# atxmega.net
KiCad netlist of a schematic drawn in Altium Designer
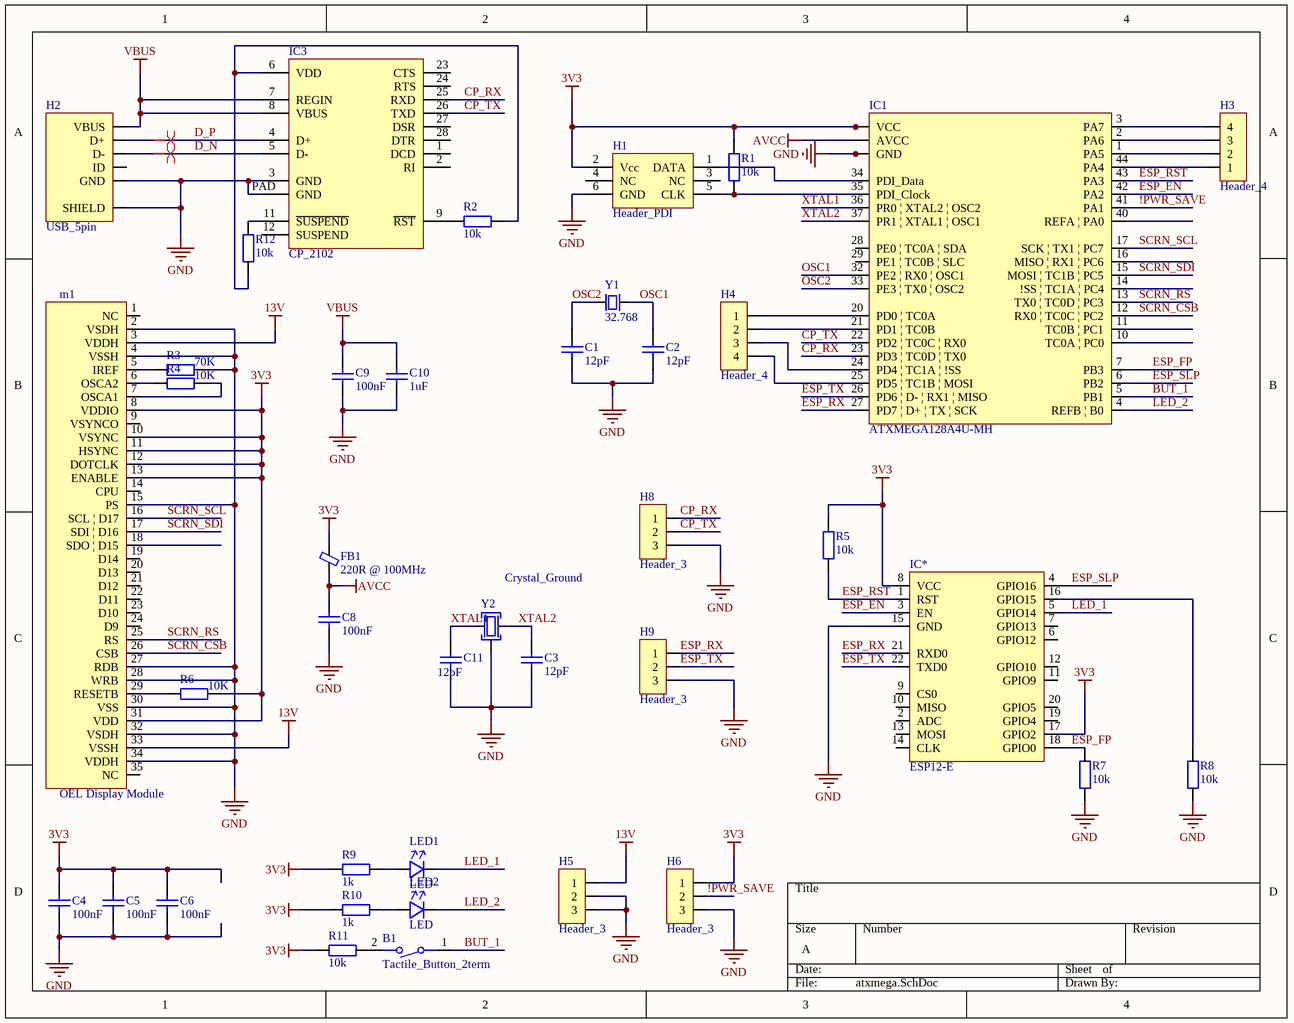
[diagram p0: atxmega.SchDoc]

(export (version "E")
  (design (tool "Eeschema 10.0.6"))
  (components
    (comp (ref "B1")
      (value "Tactile_Button_2term")
      (footprint "TACTILE_MINATUE_SMD_3.5x6mm")
      (libsource (lib "AranCustomFootprints") (part "Tactile_Button_2term"))
    )
    (comp (ref "C1")
      (value "12pF")
      (footprint "C0402")
      (description "Schematic symbol of a capacitor")
      (libsource (lib "AranCustomFootprints") (part "Capacitor"))
    )
    (comp (ref "C2")
      (value "12pF")
      (footprint "C0402")
      (description "Schematic symbol of a capacitor")
      (libsource (lib "AranCustomFootprints") (part "Capacitor"))
    )
    (comp (ref "C3")
      (value "12pF")
      (footprint "C0402")
      (description "Schematic symbol of a capacitor")
      (libsource (lib "AranCustomFootprints") (part "Capacitor"))
    )
    (comp (ref "C4")
      (value "100nF")
      (footprint "C0603")
      (description "Schematic symbol of a capacitor")
      (libsource (lib "AranCustomFootprints") (part "Capacitor"))
    )
    (comp (ref "C5")
      (value "100nF")
      (footprint "C0603")
      (description "Schematic symbol of a capacitor")
      (libsource (lib "AranCustomFootprints") (part "Capacitor"))
    )
    (comp (ref "C6")
      (value "100nF")
      (footprint "C0603")
      (description "Schematic symbol of a capacitor")
      (libsource (lib "AranCustomFootprints") (part "Capacitor"))
    )
    (comp (ref "C8")
      (value "100nF")
      (footprint "C0603")
      (description "Schematic symbol of a capacitor")
      (libsource (lib "AranCustomFootprints") (part "Capacitor"))
    )
    (comp (ref "C9")
      (value "100nF")
      (footprint "C0603")
      (description "Schematic symbol of a capacitor")
      (libsource (lib "AranCustomFootprints") (part "Capacitor"))
    )
    (comp (ref "C10")
      (value "1uF")
      (footprint "C0603")
      (description "Schematic symbol of a capacitor")
      (libsource (lib "AranCustomFootprints") (part "Capacitor"))
    )
    (comp (ref "C11")
      (value "12pF")
      (footprint "C0402")
      (description "Schematic symbol of a capacitor")
      (libsource (lib "AranCustomFootprints") (part "Capacitor"))
    )
    (comp (ref "FB1")
      (value "220R @ 100MHz")
      (footprint "L0805")
      (libsource (lib "AranCustomFootprints") (part "Ferrite"))
    )
    (comp (ref "H1")
      (value "Header_PDI")
      (footprint "6-HEADER_BOXED")
      (description "6-pin Boxed header with pinout used for PDI programming by Atmel programmers")
      (libsource (lib "AranCustomFootprints") (part "Header_PDI"))
    )
    (comp (ref "H2")
      (value "USB_5pin")
      (footprint "USB_Micro_B_RECEPTABLE_FCI")
      (description "5 Pins USB Connector")
      (libsource (lib "AranCustomFootprints") (part "USB_5pin"))
    )
    (comp (ref "H3")
      (value "Header_4")
      (footprint "Header_MALE_4")
      (description "Generic 4pin header symbol")
      (libsource (lib "AranCustomFootprints") (part "Header_4"))
    )
    (comp (ref "H4")
      (value "Header_4")
      (footprint "Header_MALE_4")
      (description "Generic 4pin header symbol")
      (libsource (lib "") (part "Header_4_1"))
    )
    (comp (ref "H5")
      (value "Header_3")
      (footprint "Header_MALE_3")
      (description "Generic 3pin header symbol")
      (libsource (lib "AranCustomFootprints") (part "Header_3"))
    )
    (comp (ref "H6")
      (value "Header_3")
      (footprint "Header_MALE_3")
      (description "Generic 3pin header symbol")
      (libsource (lib "AranCustomFootprints") (part "Header_3"))
    )
    (comp (ref "H8")
      (value "Header_3")
      (footprint "Header_MALE_3")
      (description "Generic 3pin header symbol")
      (libsource (lib "AranCustomFootprints") (part "Header_3"))
    )
    (comp (ref "H9")
      (value "Header_3")
      (footprint "Header_MALE_3")
      (description "Generic 3pin header symbol")
      (libsource (lib "AranCustomFootprints") (part "Header_3"))
    )
    (comp (ref "IC*") (value "ESP12-E") (footprint "ESP12-E") (libsource (lib "elmarlib") (part "ESP12-E")))
    (comp (ref "IC1")
      (value "ATXMEGA128A4U-MH")
      (footprint "44-VFQFN-E")
      (description "AVR AVR® XMEGA® A4U Microcontroller IC 8/16-Bit 32MHz 128KB (64K x 16) FLASH 44-VQFN (7x7)")
      (libsource (lib "elmarlib") (part "ATXMEGA128A4U-MH"))
    )
    (comp (ref "IC3")
      (value "CP_2102")
      (footprint "28-QFN_Exposed_pad")
      (description "Single chip USB to UART Bridge")
      (libsource (lib "AranCustomFootprints") (part "CP_2102"))
    )
    (comp (ref "LED1")
      (value "LED")
      (footprint "0603_LED")
      (description "Schematic symbol of a LED")
      (libsource (lib "AranCustomFootprints") (part "LED"))
    )
    (comp (ref "LED2")
      (value "LED")
      (footprint "0603_LED")
      (description "Schematic symbol of a LED")
      (libsource (lib "AranCustomFootprints") (part "LED"))
    )
    (comp (ref "m1")
      (value "OEL Display Module")
      (footprint "FFC-35-pin-0.5")
      (description "Part ID: UG-6028GDEAF01")
      (libsource (lib "elmarlib") (part "OEL Display Module"))
    )
    (comp (ref "R1")
      (value "10k")
      (footprint "R0603")
      (description "Schematic symbol of a resistor")
      (libsource (lib "AranCustomFootprints") (part "Resistor"))
    )
    (comp (ref "R2")
      (value "10k")
      (footprint "R0603")
      (description "Schematic symbol of a resistor")
      (libsource (lib "AranCustomFootprints") (part "Resistor"))
    )
    (comp (ref "R3")
      (value "70K")
      (footprint "R0603")
      (description "Schematic symbol of a resistor")
      (libsource (lib "AranCustomFootprints") (part "Resistor"))
    )
    (comp (ref "R4")
      (value "10K")
      (footprint "R0603")
      (description "Schematic symbol of a resistor")
      (libsource (lib "AranCustomFootprints") (part "Resistor"))
    )
    (comp (ref "R5")
      (value "10k")
      (footprint "R0603")
      (description "Schematic symbol of a resistor")
      (libsource (lib "AranCustomFootprints") (part "Resistor"))
    )
    (comp (ref "R6")
      (value "10K")
      (footprint "R0603")
      (description "Schematic symbol of a resistor")
      (libsource (lib "AranCustomFootprints") (part "Resistor"))
    )
    (comp (ref "R7")
      (value "10k")
      (footprint "R0603")
      (description "Schematic symbol of a resistor")
      (libsource (lib "AranCustomFootprints") (part "Resistor"))
    )
    (comp (ref "R8")
      (value "10k")
      (footprint "R0603")
      (description "Schematic symbol of a resistor")
      (libsource (lib "AranCustomFootprints") (part "Resistor"))
    )
    (comp (ref "R9")
      (value "1k")
      (footprint "R0603")
      (description "Schematic symbol of a resistor")
      (libsource (lib "AranCustomFootprints") (part "Resistor"))
    )
    (comp (ref "R10")
      (value "1k")
      (footprint "R0603")
      (description "Schematic symbol of a resistor")
      (libsource (lib "AranCustomFootprints") (part "Resistor"))
    )
    (comp (ref "R11")
      (value "10k")
      (footprint "R0603")
      (description "Schematic symbol of a resistor")
      (libsource (lib "AranCustomFootprints") (part "Resistor"))
    )
    (comp (ref "R12")
      (value "10k")
      (footprint "R0603")
      (description "Schematic symbol of a resistor")
      (libsource (lib "AranCustomFootprints") (part "Resistor"))
    )
    (comp (ref "Y1")
      (value "32.768")
      (footprint "crystal_6.2x2.1x2.1")
      (description "32.768kHz ±20ppm Crystal 12.5pF 35 kOhm -10°C ~ 60°C Through Hole Cylindrical Can, Radial")
      (libsource (lib "elmarlib") (part "Abracon LLC AB26T-32.768KHZ"))
    )
    (comp (ref "Y2")
      (value "Crystal_Ground")
      (footprint "Crystal_3.2x2.5")
      (description "Schematic symbol of a 2pin crystal with case connection")
      (libsource (lib "AranCustomFootprints") (part "Crystal_Ground"))
    )
  )
  (nets
    (net (code "1") (name "/!PWR_SAVE") (class "Default")
      (node (ref "H6") (pin "2") (pinfunction "2_2") (pintype "passive"))
      (node (ref "IC1") (pin "41") (pinfunction "PA1_41") (pintype "passive"))
    )
    (net (code "2") (name "/BUT_1") (class "Default")
      (node (ref "B1") (pin "1") (pintype "passive"))
      (node (ref "IC1") (pin "5") (pinfunction "PB1_5") (pintype "passive"))
    )
    (net (code "3") (name "/CP_RX") (class "Default")
      (node (ref "H8") (pin "1") (pinfunction "1_1") (pintype "passive"))
      (node (ref "IC1") (pin "23") (pinfunction "PD3_¦_TC0D_¦_TX0_23") (pintype "passive"))
      (node (ref "IC3") (pin "25") (pinfunction "RXD_25") (pintype "passive"))
    )
    (net (code "4") (name "/CP_TX") (class "Default")
      (node (ref "H8") (pin "2") (pinfunction "2_2") (pintype "passive"))
      (node (ref "IC1") (pin "22") (pinfunction "PD2_¦_TC0C_¦_RX0_22") (pintype "passive"))
      (node (ref "IC3") (pin "26") (pinfunction "TXD_26") (pintype "passive"))
    )
    (net (code "5") (name "/D_N") (class "Default")
      (node (ref "H2") (pin "2") (pinfunction "D-_2") (pintype "passive"))
      (node (ref "IC3") (pin "5") (pinfunction "D-_5") (pintype "passive"))
    )
    (net (code "6") (name "/D_P") (class "Default")
      (node (ref "H2") (pin "3") (pinfunction "D+_3") (pintype "passive"))
      (node (ref "IC3") (pin "4") (pinfunction "D+_4") (pintype "passive"))
    )
    (net (code "7") (name "/ESP_EN") (class "Default")
      (node (ref "IC*") (pin "3") (pinfunction "EN_3") (pintype "passive"))
      (node (ref "IC1") (pin "42") (pinfunction "PA2_42") (pintype "passive"))
    )
    (net (code "8") (name "/ESP_FP") (class "Default")
      (node (ref "IC*") (pin "18") (pinfunction "GPIO0_18") (pintype "passive"))
      (node (ref "IC1") (pin "7") (pinfunction "PB3_7") (pintype "passive"))
      (node (ref "R7") (pin "1") (pinfunction "1_1") (pintype "passive"))
    )
    (net (code "9") (name "/ESP_RST") (class "Default")
      (node (ref "IC*") (pin "1") (pinfunction "RST_1") (pintype "passive"))
      (node (ref "IC1") (pin "43") (pinfunction "PA3_43") (pintype "passive"))
      (node (ref "R5") (pin "2") (pinfunction "2_2") (pintype "passive"))
    )
    (net (code "10") (name "/ESP_RX") (class "Default")
      (node (ref "H9") (pin "1") (pinfunction "1_1") (pintype "passive"))
      (node (ref "IC*") (pin "21") (pinfunction "RXD0_21") (pintype "passive"))
      (node (ref "IC1") (pin "27") (pinfunction "PD7_¦_D+_¦_TX_¦_SCK_27") (pintype "passive"))
    )
    (net (code "11") (name "/ESP_SLP") (class "Default")
      (node (ref "IC*") (pin "4") (pinfunction "GPIO16_4") (pintype "passive"))
      (node (ref "IC1") (pin "6") (pinfunction "PB2_6") (pintype "passive"))
    )
    (net (code "12") (name "/ESP_TX") (class "Default")
      (node (ref "H9") (pin "2") (pinfunction "2_2") (pintype "passive"))
      (node (ref "IC*") (pin "22") (pinfunction "TXD0_22") (pintype "passive"))
      (node (ref "IC1") (pin "26") (pinfunction "PD6_¦_D-_¦_RX1_¦_MISO_26") (pintype "passive"))
    )
    (net (code "13") (name "/LED_1") (class "Default")
      (node (ref "IC*") (pin "5") (pinfunction "GPIO14_5") (pintype "passive"))
      (node (ref "LED1") (pin "C") (pinfunction "Cathode_C") (pintype "passive"))
    )
    (net (code "14") (name "/LED_2") (class "Default")
      (node (ref "IC1") (pin "4") (pinfunction "REFB_¦_B0_4") (pintype "passive"))
      (node (ref "LED2") (pin "C") (pinfunction "Cathode_C") (pintype "passive"))
    )
    (net (code "15") (name "/OSC1") (class "Default")
      (node (ref "C2") (pin "1") (pinfunction "1_1") (pintype "passive"))
      (node (ref "IC1") (pin "32") (pinfunction "PE2_¦_RX0_¦_OSC1_32") (pintype "passive"))
      (node (ref "Y1") (pin "0") (pinfunction "XTAL2_0") (pintype "passive"))
    )
    (net (code "16") (name "/OSC2") (class "Default")
      (node (ref "C1") (pin "1") (pinfunction "1_1") (pintype "passive"))
      (node (ref "IC1") (pin "33") (pinfunction "PE3_¦_TX0_¦_OSC2_33") (pintype "passive"))
      (node (ref "Y1") (pin "1") (pinfunction "XTAL1_1") (pintype "passive"))
    )
    (net (code "17") (name "/SCRN_CSB") (class "Default")
      (node (ref "IC1") (pin "12") (pinfunction "RX0_¦_TC0C_¦_PC2_12") (pintype "passive"))
      (node (ref "m1") (pin "26") (pinfunction "CSB_26") (pintype "passive"))
    )
    (net (code "18") (name "/SCRN_RS") (class "Default")
      (node (ref "IC1") (pin "13") (pinfunction "TX0_¦_TC0D_¦_PC3_13") (pintype "passive"))
      (node (ref "m1") (pin "25") (pinfunction "RS_25") (pintype "passive"))
    )
    (net (code "19") (name "/SCRN_SCL") (class "Default")
      (node (ref "IC1") (pin "17") (pinfunction "SCK_¦_TX1_¦_PC7_17") (pintype "passive"))
      (node (ref "m1") (pin "16") (pinfunction "SCL_¦_D17_16") (pintype "passive"))
    )
    (net (code "20") (name "/SCRN_SDI") (class "Default")
      (node (ref "IC1") (pin "15") (pinfunction "MOSI_¦_TC1B_¦_PC5_15") (pintype "passive"))
      (node (ref "m1") (pin "17") (pinfunction "SDI_¦_D16_17") (pintype "passive"))
    )
    (net (code "21") (name "/XTAL1") (class "Default")
      (node (ref "C11") (pin "1") (pinfunction "1_1") (pintype "passive"))
      (node (ref "IC1") (pin "36") (pinfunction "PR0_¦_XTAL2_¦_OSC2_36") (pintype "passive"))
      (node (ref "Y2") (pin "1") (pinfunction "1_1") (pintype "passive"))
    )
    (net (code "22") (name "/XTAL2") (class "Default")
      (node (ref "C3") (pin "1") (pinfunction "1_1") (pintype "passive"))
      (node (ref "IC1") (pin "37") (pinfunction "PR1_¦_XTAL1_¦_OSC1_37") (pintype "passive"))
      (node (ref "Y2") (pin "3") (pinfunction "3_3") (pintype "passive"))
    )
    (net (code "23") (name "3V3") (class "Default")
      (node (ref "C4") (pin "1") (pinfunction "1_1") (pintype "passive"))
      (node (ref "C5") (pin "1") (pinfunction "1_1") (pintype "passive"))
      (node (ref "C6") (pin "1") (pinfunction "1_1") (pintype "passive"))
      (node (ref "FB1") (pin "2") (pinfunction "2_2") (pintype "passive"))
      (node (ref "H1") (pin "2") (pinfunction "Vcc_2") (pintype "passive"))
      (node (ref "H6") (pin "1") (pinfunction "1_1") (pintype "passive"))
      (node (ref "IC*") (pin "17") (pinfunction "GPIO2_17") (pintype "passive"))
      (node (ref "IC*") (pin "8") (pinfunction "VCC_8") (pintype "passive"))
      (node (ref "IC1") (pin "19") (pinfunction "VCC_19") (pintype "passive"))
      (node (ref "IC1") (pin "31") (pinfunction "VCC_31") (pintype "passive"))
      (node (ref "IC1") (pin "9") (pinfunction "VCC_9") (pintype "passive"))
      (node (ref "R1") (pin "1") (pinfunction "1_1") (pintype "passive"))
      (node (ref "R10") (pin "1") (pinfunction "1_1") (pintype "passive"))
      (node (ref "R11") (pin "1") (pinfunction "1_1") (pintype "passive"))
      (node (ref "R5") (pin "1") (pinfunction "1_1") (pintype "passive"))
      (node (ref "R6") (pin "1") (pinfunction "1_1") (pintype "passive"))
      (node (ref "R9") (pin "1") (pinfunction "1_1") (pintype "passive"))
      (node (ref "m1") (pin "10") (pinfunction "VSYNC_10") (pintype "passive"))
      (node (ref "m1") (pin "11") (pinfunction "HSYNC_11") (pintype "passive"))
      (node (ref "m1") (pin "12") (pinfunction "DOTCLK_12") (pintype "passive"))
      (node (ref "m1") (pin "13") (pinfunction "ENABLE_13") (pintype "passive"))
      (node (ref "m1") (pin "31") (pinfunction "VDD_31") (pintype "passive"))
      (node (ref "m1") (pin "8") (pinfunction "VDDIO_8") (pintype "passive"))
    )
    (net (code "24") (name "13V") (class "Default")
      (node (ref "H5") (pin "1") (pinfunction "1_1") (pintype "passive"))
      (node (ref "m1") (pin "3") (pinfunction "VDDH_3") (pintype "passive"))
      (node (ref "m1") (pin "33") (pinfunction "VSSH_33") (pintype "passive"))
    )
    (net (code "25") (name "AVCC") (class "Default")
      (node (ref "C8") (pin "1") (pinfunction "1_1") (pintype "passive"))
      (node (ref "FB1") (pin "1") (pinfunction "1_1") (pintype "passive"))
      (node (ref "IC1") (pin "39") (pinfunction "AVCC_39") (pintype "passive"))
    )
    (net (code "26") (name "GND") (class "Default")
      (node (ref "C1") (pin "2") (pinfunction "2_2") (pintype "passive"))
      (node (ref "C10") (pin "1") (pinfunction "1_1") (pintype "passive"))
      (node (ref "C11") (pin "2") (pinfunction "2_2") (pintype "passive"))
      (node (ref "C2") (pin "2") (pinfunction "2_2") (pintype "passive"))
      (node (ref "C3") (pin "2") (pinfunction "2_2") (pintype "passive"))
      (node (ref "C4") (pin "2") (pinfunction "2_2") (pintype "passive"))
      (node (ref "C5") (pin "2") (pinfunction "2_2") (pintype "passive"))
      (node (ref "C6") (pin "2") (pinfunction "2_2") (pintype "passive"))
      (node (ref "C8") (pin "2") (pinfunction "2_2") (pintype "passive"))
      (node (ref "C9") (pin "1") (pinfunction "1_1") (pintype "passive"))
      (node (ref "H1") (pin "6") (pinfunction "GND_6") (pintype "passive"))
      (node (ref "H2") (pin "5") (pinfunction "GND_5") (pintype "passive"))
      (node (ref "H2") (pin "SHIELD") (pinfunction "SHIELD_SHIELD") (pintype "passive"))
      (node (ref "H5") (pin "2") (pinfunction "2_2") (pintype "passive"))
      (node (ref "H5") (pin "3") (pinfunction "3_3") (pintype "passive"))
      (node (ref "H6") (pin "3") (pinfunction "3_3") (pintype "passive"))
      (node (ref "H8") (pin "3") (pinfunction "3_3") (pintype "passive"))
      (node (ref "H9") (pin "3") (pinfunction "3_3") (pintype "passive"))
      (node (ref "IC*") (pin "15") (pinfunction "GND_15") (pintype "passive"))
      (node (ref "IC1") (pin "18") (pinfunction "GND_18") (pintype "passive"))
      (node (ref "IC1") (pin "30") (pinfunction "GND_30") (pintype "passive"))
      (node (ref "IC1") (pin "38") (pinfunction "GND_38") (pintype "passive"))
      (node (ref "IC1") (pin "45") (pinfunction "GND_45") (pintype "passive"))
      (node (ref "IC1") (pin "8") (pinfunction "GND_8") (pintype "passive"))
      (node (ref "IC3") (pin "3") (pinfunction "GND_3") (pintype "passive"))
      (node (ref "IC3") (pin "PAD") (pinfunction "GND_PAD") (pintype "passive"))
      (node (ref "R3") (pin "1") (pinfunction "1_1") (pintype "passive"))
      (node (ref "R7") (pin "2") (pinfunction "2_2") (pintype "passive"))
      (node (ref "R8") (pin "2") (pinfunction "2_2") (pintype "passive"))
      (node (ref "Y2") (pin "2") (pinfunction "2_2") (pintype "passive"))
      (node (ref "m1") (pin "15") (pinfunction "PS_15") (pintype "passive"))
      (node (ref "m1") (pin "2") (pinfunction "VSDH_2") (pintype "passive"))
      (node (ref "m1") (pin "27") (pinfunction "RDB_27") (pintype "passive"))
      (node (ref "m1") (pin "28") (pinfunction "WRB_28") (pintype "passive"))
      (node (ref "m1") (pin "30") (pinfunction "VSS_30") (pintype "passive"))
      (node (ref "m1") (pin "32") (pinfunction "VSDH_32") (pintype "passive"))
      (node (ref "m1") (pin "34") (pinfunction "VDDH_34") (pintype "passive"))
      (node (ref "m1") (pin "4") (pinfunction "VSSH_4") (pintype "passive"))
    )
    (net (code "27") (name "Net-(B1-Pad2)") (class "Default")
      (node (ref "B1") (pin "2") (pintype "passive"))
      (node (ref "R11") (pin "2") (pinfunction "2_2") (pintype "passive"))
    )
    (net (code "28") (name "Net-(H1-CLK)") (class "Default")
      (node (ref "H1") (pin "5") (pinfunction "CLK_5") (pintype "passive"))
      (node (ref "IC1") (pin "35") (pinfunction "PDI_Clock_35") (pintype "passive"))
      (node (ref "R1") (pin "2") (pinfunction "2_2") (pintype "passive"))
    )
    (net (code "29") (name "Net-(H1-DATA)") (class "Default")
      (node (ref "H1") (pin "1") (pinfunction "DATA_1") (pintype "passive"))
      (node (ref "IC1") (pin "34") (pinfunction "PDI_Data_34") (pintype "passive"))
    )
    (net (code "30") (name "Net-(IC*-GPIO15)") (class "Default")
      (node (ref "IC*") (pin "16") (pinfunction "GPIO15_16") (pintype "passive"))
      (node (ref "R8") (pin "1") (pinfunction "1_1") (pintype "passive"))
    )
    (net (code "31") (name "Net-(IC1-PA4)") (class "Default")
      (node (ref "H3") (pin "1") (pinfunction "1_1") (pintype "passive"))
      (node (ref "IC1") (pin "44") (pinfunction "PA4_44") (pintype "passive"))
    )
    (net (code "32") (name "Net-(IC1-PA5)") (class "Default")
      (node (ref "H3") (pin "2") (pinfunction "2_2") (pintype "passive"))
      (node (ref "IC1") (pin "1") (pinfunction "PA5_1") (pintype "passive"))
    )
    (net (code "33") (name "Net-(IC1-PA6)") (class "Default")
      (node (ref "H3") (pin "3") (pinfunction "3_3") (pintype "passive"))
      (node (ref "IC1") (pin "2") (pinfunction "PA6_2") (pintype "passive"))
    )
    (net (code "34") (name "Net-(IC1-PA7)") (class "Default")
      (node (ref "H3") (pin "4") (pinfunction "4_4") (pintype "passive"))
      (node (ref "IC1") (pin "3") (pinfunction "PA7_3") (pintype "passive"))
    )
    (net (code "35") (name "Net-(IC1-PD0_¦_TC0A)") (class "Default")
      (node (ref "H4") (pin "1") (pinfunction "1_1") (pintype "passive"))
      (node (ref "IC1") (pin "20") (pinfunction "PD0_¦_TC0A_20") (pintype "passive"))
    )
    (net (code "36") (name "Net-(IC1-PD1_¦_TC0B)") (class "Default")
      (node (ref "H4") (pin "2") (pinfunction "2_2") (pintype "passive"))
      (node (ref "IC1") (pin "21") (pinfunction "PD1_¦_TC0B_21") (pintype "passive"))
    )
    (net (code "37") (name "Net-(IC1-PD4_¦_TC1A_¦_!SS)") (class "Default")
      (node (ref "H4") (pin "3") (pinfunction "3_3") (pintype "passive"))
      (node (ref "IC1") (pin "24") (pinfunction "PD4_¦_TC1A_¦_!SS_24") (pintype "passive"))
    )
    (net (code "38") (name "Net-(IC1-PD5_¦_TC1B_¦_MOSI)") (class "Default")
      (node (ref "H4") (pin "4") (pinfunction "4_4") (pintype "passive"))
      (node (ref "IC1") (pin "25") (pinfunction "PD5_¦_TC1B_¦_MOSI_25") (pintype "passive"))
    )
    (net (code "39") (name "Net-(IC3-VDD)") (class "Default")
      (node (ref "IC3") (pin "6") (pinfunction "VDD_6") (pintype "passive"))
      (node (ref "R12") (pin "2") (pinfunction "2_2") (pintype "passive"))
      (node (ref "R2") (pin "1") (pinfunction "1_1") (pintype "passive"))
    )
    (net (code "40") (name "Net-(IC3-~{RST})") (class "Default")
      (node (ref "IC3") (pin "9") (pinfunction "~{RST}_9") (pintype "passive"))
      (node (ref "R2") (pin "2") (pinfunction "2_2") (pintype "passive"))
    )
    (net (code "41") (name "Net-(IC3-~{SUSPEND})") (class "Default")
      (node (ref "IC3") (pin "11") (pinfunction "~{SUSPEND}_11") (pintype "passive"))
      (node (ref "R12") (pin "1") (pinfunction "1_1") (pintype "passive"))
    )
    (net (code "42") (name "Net-(LED1-Anode)") (class "Default")
      (node (ref "LED1") (pin "A") (pinfunction "Anode_A") (pintype "passive"))
      (node (ref "R9") (pin "2") (pinfunction "2_2") (pintype "passive"))
    )
    (net (code "43") (name "Net-(LED2-Anode)") (class "Default")
      (node (ref "LED2") (pin "A") (pinfunction "Anode_A") (pintype "passive"))
      (node (ref "R10") (pin "2") (pinfunction "2_2") (pintype "passive"))
    )
    (net (code "44") (name "Net-(m1-IREF)") (class "Default")
      (node (ref "R3") (pin "2") (pinfunction "2_2") (pintype "passive"))
      (node (ref "m1") (pin "5") (pinfunction "IREF_5") (pintype "passive"))
    )
    (net (code "45") (name "Net-(m1-OSCA1)") (class "Default")
      (node (ref "R4") (pin "1") (pinfunction "1_1") (pintype "passive"))
      (node (ref "m1") (pin "7") (pinfunction "OSCA1_7") (pintype "passive"))
    )
    (net (code "46") (name "Net-(m1-OSCA2)") (class "Default")
      (node (ref "R4") (pin "2") (pinfunction "2_2") (pintype "passive"))
      (node (ref "m1") (pin "6") (pinfunction "OSCA2_6") (pintype "passive"))
    )
    (net (code "47") (name "Net-(m1-RESETB)") (class "Default")
      (node (ref "R6") (pin "2") (pinfunction "2_2") (pintype "passive"))
      (node (ref "m1") (pin "29") (pinfunction "RESETB_29") (pintype "passive"))
    )
    (net (code "48") (name "VBUS") (class "Default")
      (node (ref "C10") (pin "2") (pinfunction "2_2") (pintype "passive"))
      (node (ref "C9") (pin "2") (pinfunction "2_2") (pintype "passive"))
      (node (ref "H2") (pin "1") (pinfunction "VBUS_1") (pintype "passive"))
      (node (ref "IC3") (pin "7") (pinfunction "REGIN_7") (pintype "passive"))
      (node (ref "IC3") (pin "8") (pinfunction "VBUS_8") (pintype "passive"))
    )
    (net (code "49") (name "unconnected-(H1-NC-Pad3)") (class "Default")
      (node (ref "H1") (pin "3") (pinfunction "NC_3") (pintype "passive"))
    )
    (net (code "50") (name "unconnected-(H1-NC-Pad4)") (class "Default")
      (node (ref "H1") (pin "4") (pinfunction "NC_4") (pintype "passive"))
    )
    (net (code "51") (name "unconnected-(H2-ID-Pad4)") (class "Default")
      (node (ref "H2") (pin "4") (pinfunction "ID_4") (pintype "passive"))
    )
    (net (code "52") (name "unconnected-(IC*-ADC-Pad2)") (class "Default")
      (node (ref "IC*") (pin "2") (pinfunction "ADC_2") (pintype "passive"))
    )
    (net (code "53") (name "unconnected-(IC*-CLK-Pad14)") (class "Default")
      (node (ref "IC*") (pin "14") (pinfunction "CLK_14") (pintype "passive"))
    )
    (net (code "54") (name "unconnected-(IC*-CS0-Pad9)") (class "Default")
      (node (ref "IC*") (pin "9") (pinfunction "CS0_9") (pintype "passive"))
    )
    (net (code "55") (name "unconnected-(IC*-GPIO4-Pad19)") (class "Default")
      (node (ref "IC*") (pin "19") (pinfunction "GPIO4_19") (pintype "passive"))
    )
    (net (code "56") (name "unconnected-(IC*-GPIO5-Pad20)") (class "Default")
      (node (ref "IC*") (pin "20") (pinfunction "GPIO5_20") (pintype "passive"))
    )
    (net (code "57") (name "unconnected-(IC*-GPIO9-Pad11)") (class "Default")
      (node (ref "IC*") (pin "11") (pinfunction "GPIO9_11") (pintype "passive"))
    )
    (net (code "58") (name "unconnected-(IC*-GPIO10-Pad12)") (class "Default")
      (node (ref "IC*") (pin "12") (pinfunction "GPIO10_12") (pintype "passive"))
    )
    (net (code "59") (name "unconnected-(IC*-GPIO12-Pad6)") (class "Default")
      (node (ref "IC*") (pin "6") (pinfunction "GPIO12_6") (pintype "passive"))
    )
    (net (code "60") (name "unconnected-(IC*-GPIO13-Pad7)") (class "Default")
      (node (ref "IC*") (pin "7") (pinfunction "GPIO13_7") (pintype "passive"))
    )
    (net (code "61") (name "unconnected-(IC*-MISO-Pad10)") (class "Default")
      (node (ref "IC*") (pin "10") (pinfunction "MISO_10") (pintype "passive"))
    )
    (net (code "62") (name "unconnected-(IC*-MOSI-Pad13)") (class "Default")
      (node (ref "IC*") (pin "13") (pinfunction "MOSI_13") (pintype "passive"))
    )
    (net (code "63") (name "unconnected-(IC1-!SS_¦_TC1A_¦_PC4-Pad14)") (class "Default")
      (node (ref "IC1") (pin "14") (pinfunction "!SS_¦_TC1A_¦_PC4_14") (pintype "passive"))
    )
    (net (code "64") (name "unconnected-(IC1-MISO_¦_RX1_¦_PC6-Pad16)") (class "Default")
      (node (ref "IC1") (pin "16") (pinfunction "MISO_¦_RX1_¦_PC6_16") (pintype "passive"))
    )
    (net (code "65") (name "unconnected-(IC1-PE0_¦_TC0A_¦_SDA-Pad28)") (class "Default")
      (node (ref "IC1") (pin "28") (pinfunction "PE0_¦_TC0A_¦_SDA_28") (pintype "passive"))
    )
    (net (code "66") (name "unconnected-(IC1-PE1_¦_TC0B_¦_SLC-Pad29)") (class "Default")
      (node (ref "IC1") (pin "29") (pinfunction "PE1_¦_TC0B_¦_SLC_29") (pintype "passive"))
    )
    (net (code "67") (name "unconnected-(IC1-REFA_¦_PA0-Pad40)") (class "Default")
      (node (ref "IC1") (pin "40") (pinfunction "REFA_¦_PA0_40") (pintype "passive"))
    )
    (net (code "68") (name "unconnected-(IC1-TC0A_¦_PC0-Pad10)") (class "Default")
      (node (ref "IC1") (pin "10") (pinfunction "TC0A_¦_PC0_10") (pintype "passive"))
    )
    (net (code "69") (name "unconnected-(IC1-TC0B_¦_PC1-Pad11)") (class "Default")
      (node (ref "IC1") (pin "11") (pinfunction "TC0B_¦_PC1_11") (pintype "passive"))
    )
    (net (code "70") (name "unconnected-(IC3-CTS-Pad23)") (class "Default")
      (node (ref "IC3") (pin "23") (pinfunction "CTS_23") (pintype "passive"))
    )
    (net (code "71") (name "unconnected-(IC3-DCD-Pad1)") (class "Default")
      (node (ref "IC3") (pin "1") (pinfunction "DCD_1") (pintype "passive"))
    )
    (net (code "72") (name "unconnected-(IC3-DSR-Pad27)") (class "Default")
      (node (ref "IC3") (pin "27") (pinfunction "DSR_27") (pintype "passive"))
    )
    (net (code "73") (name "unconnected-(IC3-DTR-Pad28)") (class "Default")
      (node (ref "IC3") (pin "28") (pinfunction "DTR_28") (pintype "passive"))
    )
    (net (code "74") (name "unconnected-(IC3-RI-Pad2)") (class "Default")
      (node (ref "IC3") (pin "2") (pinfunction "RI_2") (pintype "passive"))
    )
    (net (code "75") (name "unconnected-(IC3-RTS-Pad24)") (class "Default")
      (node (ref "IC3") (pin "24") (pinfunction "RTS_24") (pintype "passive"))
    )
    (net (code "76") (name "unconnected-(IC3-SUSPEND-Pad12)") (class "Default")
      (node (ref "IC3") (pin "12") (pinfunction "SUSPEND_12") (pintype "passive"))
    )
    (net (code "77") (name "unconnected-(m1-CPU-Pad14)") (class "Default")
      (node (ref "m1") (pin "14") (pinfunction "CPU_14") (pintype "passive"))
    )
    (net (code "78") (name "unconnected-(m1-D9-Pad24)") (class "Default")
      (node (ref "m1") (pin "24") (pinfunction "D9_24") (pintype "passive"))
    )
    (net (code "79") (name "unconnected-(m1-D10-Pad23)") (class "Default")
      (node (ref "m1") (pin "23") (pinfunction "D10_23") (pintype "passive"))
    )
    (net (code "80") (name "unconnected-(m1-D11-Pad22)") (class "Default")
      (node (ref "m1") (pin "22") (pinfunction "D11_22") (pintype "passive"))
    )
    (net (code "81") (name "unconnected-(m1-D12-Pad21)") (class "Default")
      (node (ref "m1") (pin "21") (pinfunction "D12_21") (pintype "passive"))
    )
    (net (code "82") (name "unconnected-(m1-D13-Pad20)") (class "Default")
      (node (ref "m1") (pin "20") (pinfunction "D13_20") (pintype "passive"))
    )
    (net (code "83") (name "unconnected-(m1-D14-Pad19)") (class "Default")
      (node (ref "m1") (pin "19") (pinfunction "D14_19") (pintype "passive"))
    )
    (net (code "84") (name "unconnected-(m1-NC-Pad1)") (class "Default")
      (node (ref "m1") (pin "1") (pinfunction "NC_1") (pintype "passive"))
    )
    (net (code "85") (name "unconnected-(m1-NC-Pad35)") (class "Default")
      (node (ref "m1") (pin "35") (pinfunction "NC_35") (pintype "passive"))
    )
    (net (code "86") (name "unconnected-(m1-SDO_¦_D15-Pad18)") (class "Default")
      (node (ref "m1") (pin "18") (pinfunction "SDO_¦_D15_18") (pintype "passive"))
    )
    (net (code "87") (name "unconnected-(m1-VSYNCO-Pad9)") (class "Default")
      (node (ref "m1") (pin "9") (pinfunction "VSYNCO_9") (pintype "passive"))
    )
  )
)
